# nola8.net
KiCad netlist of a schematic drawn in EAGLE
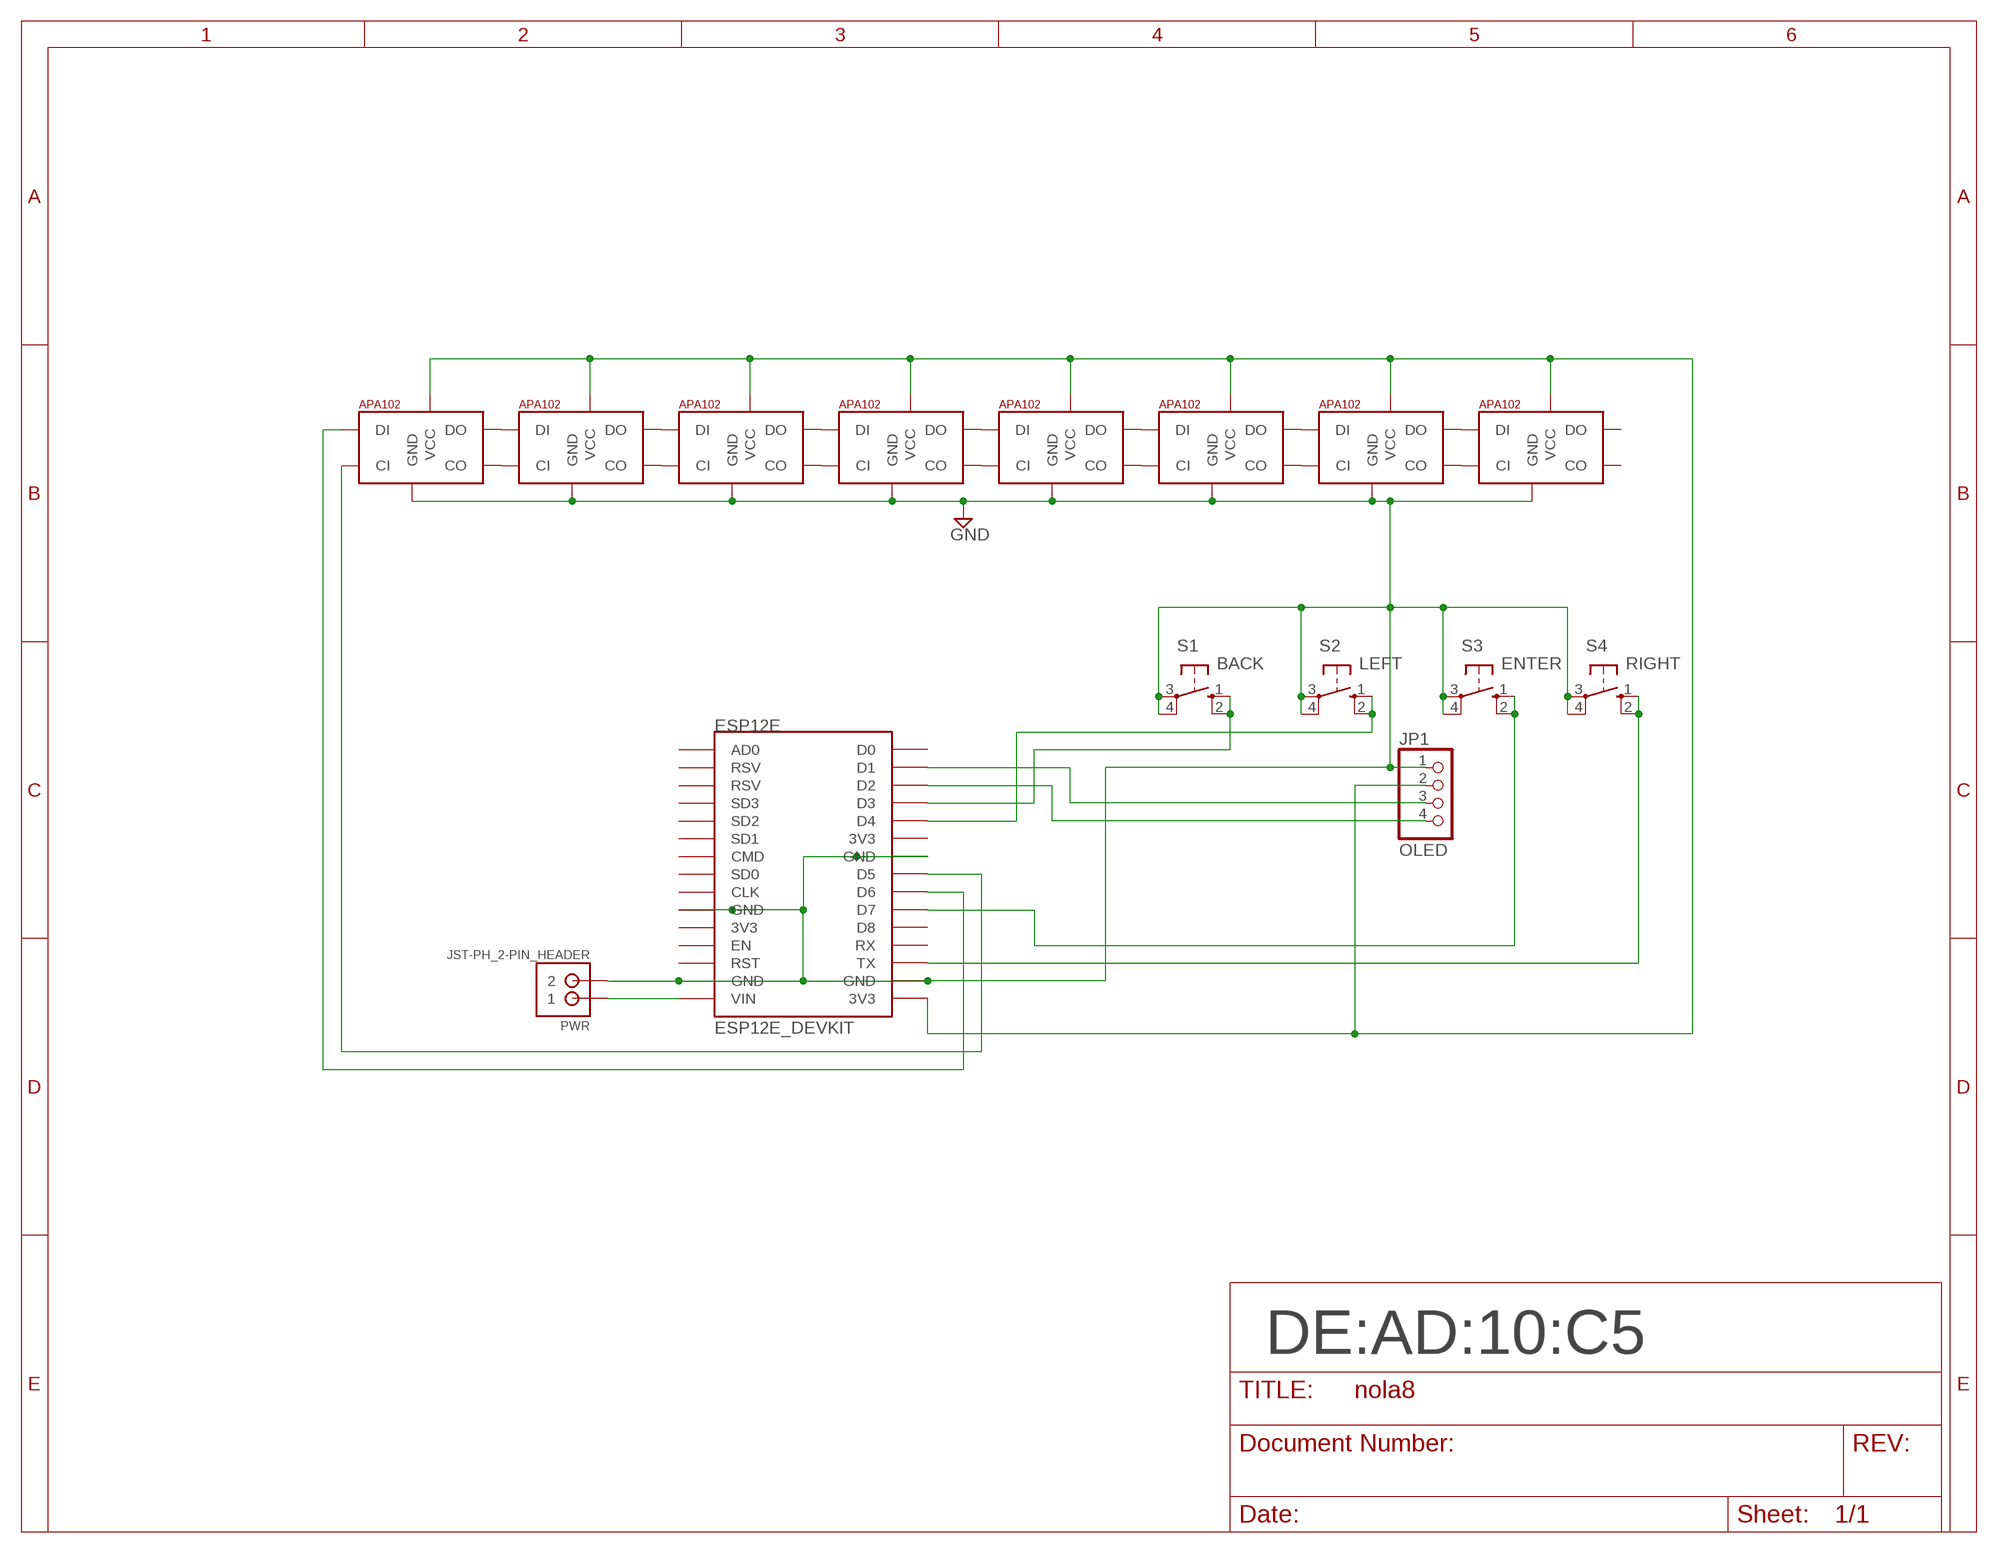
[diagram p0: schematic, sheet 1]

(export (version "E")
  (design (tool "Eeschema 10.0.6"))
  (components
    (comp (ref "ESP12E")
      (value "ESP12E_DEVKIT")
      (footprint "eagle-import:ESP12E_DEVKIT")
      (libsource (lib "eagle-import") (part "ESP12E_DEVKIT"))
    )
    (comp (ref "JP1")
      (value "OLED")
      (footprint "eagle-import:1X04")
      (libsource (lib "eagle-import") (part "PINHD-1X4"))
    )
    (comp (ref "LED1")
      (value "APA1025050")
      (footprint "eagle-import:APA102_5050")
      (libsource (lib "eagle-import") (part "APA1025050"))
    )
    (comp (ref "LED2")
      (value "APA1025050")
      (footprint "eagle-import:APA102_5050")
      (libsource (lib "eagle-import") (part "APA1025050"))
    )
    (comp (ref "LED3")
      (value "APA1025050")
      (footprint "eagle-import:APA102_5050")
      (libsource (lib "eagle-import") (part "APA1025050"))
    )
    (comp (ref "LED4")
      (value "APA1025050")
      (footprint "eagle-import:APA102_5050")
      (libsource (lib "eagle-import") (part "APA1025050"))
    )
    (comp (ref "LED5")
      (value "APA1025050")
      (footprint "eagle-import:APA102_5050")
      (libsource (lib "eagle-import") (part "APA1025050"))
    )
    (comp (ref "LED6")
      (value "APA1025050")
      (footprint "eagle-import:APA102_5050")
      (libsource (lib "eagle-import") (part "APA1025050"))
    )
    (comp (ref "LED7")
      (value "APA1025050")
      (footprint "eagle-import:APA102_5050")
      (libsource (lib "eagle-import") (part "APA1025050"))
    )
    (comp (ref "LED8")
      (value "APA1025050")
      (footprint "eagle-import:APA102_5050")
      (libsource (lib "eagle-import") (part "APA1025050"))
    )
    (comp (ref "PWR")
      (value "JST-PH_2-PIN_HEADER")
      (footprint "eagle-import:JST_B2B-PH_HEADER")
      (libsource (lib "eagle-import") (part "JST-PH_2-PIN_HEADER"))
    )
    (comp (ref "S1")
      (value "BACK")
      (footprint "eagle-import:B3F-10XX")
      (fields (field (name "MPN") "B3F-1000"))
      (libsource (lib "eagle-import") (part "10-XX"))
    )
    (comp (ref "S2")
      (value "LEFT")
      (footprint "eagle-import:B3F-10XX")
      (fields (field (name "MPN") "B3F-1000"))
      (libsource (lib "eagle-import") (part "10-XX"))
    )
    (comp (ref "S3")
      (value "ENTER")
      (footprint "eagle-import:B3F-10XX")
      (fields (field (name "MPN") "B3F-1000"))
      (libsource (lib "eagle-import") (part "10-XX"))
    )
    (comp (ref "S4")
      (value "RIGHT")
      (footprint "eagle-import:B3F-10XX")
      (fields (field (name "MPN") "B3F-1000"))
      (libsource (lib "eagle-import") (part "10-XX"))
    )
  )
  (nets
    (net (code "1") (name "GND") (class "Default")
      (node (ref "ESP12E") (pin "GND@0") (pinfunction "GND_GND@0") (pintype "bidirectional"))
      (node (ref "ESP12E") (pin "GND@1") (pinfunction "GND_GND@1") (pintype "bidirectional"))
      (node (ref "ESP12E") (pin "GND@2") (pinfunction "GND_GND@2") (pintype "bidirectional"))
      (node (ref "ESP12E") (pin "GND@3") (pinfunction "GND_GND@3") (pintype "bidirectional"))
      (node (ref "JP1") (pin "1") (pinfunction "1_1") (pintype "passive"))
      (node (ref "LED1") (pin "6") (pinfunction "GND_6") (pintype "bidirectional"))
      (node (ref "LED2") (pin "6") (pinfunction "GND_6") (pintype "bidirectional"))
      (node (ref "LED3") (pin "6") (pinfunction "GND_6") (pintype "bidirectional"))
      (node (ref "LED4") (pin "6") (pinfunction "GND_6") (pintype "bidirectional"))
      (node (ref "LED5") (pin "6") (pinfunction "GND_6") (pintype "bidirectional"))
      (node (ref "LED6") (pin "6") (pinfunction "GND_6") (pintype "bidirectional"))
      (node (ref "LED7") (pin "6") (pinfunction "GND_6") (pintype "bidirectional"))
      (node (ref "LED8") (pin "6") (pinfunction "GND_6") (pintype "bidirectional"))
      (node (ref "PWR") (pin "P2") (pinfunction "2_P2") (pintype "bidirectional"))
      (node (ref "S1") (pin "3") (pinfunction "P_3") (pintype "passive"))
      (node (ref "S1") (pin "4") (pinfunction "P1_4") (pintype "passive"))
      (node (ref "S2") (pin "3") (pinfunction "P_3") (pintype "passive"))
      (node (ref "S2") (pin "4") (pinfunction "P1_4") (pintype "passive"))
      (node (ref "S3") (pin "3") (pinfunction "P_3") (pintype "passive"))
      (node (ref "S3") (pin "4") (pinfunction "P1_4") (pintype "passive"))
      (node (ref "S4") (pin "3") (pinfunction "P_3") (pintype "passive"))
      (node (ref "S4") (pin "4") (pinfunction "P1_4") (pintype "passive"))
    )
    (net (code "2") (name "Net-(ESP12E-PadD1)") (class "Default")
      (node (ref "ESP12E") (pin "D1") (pinfunction "D1_D1") (pintype "bidirectional"))
      (node (ref "JP1") (pin "3") (pinfunction "3_3") (pintype "passive"))
    )
    (net (code "3") (name "Net-(ESP12E-PadD2)") (class "Default")
      (node (ref "ESP12E") (pin "D2") (pinfunction "D2_D2") (pintype "bidirectional"))
      (node (ref "JP1") (pin "4") (pinfunction "4_4") (pintype "passive"))
    )
    (net (code "4") (name "Net-(LED1-CI)") (class "Default")
      (node (ref "ESP12E") (pin "D5") (pinfunction "D5_D5") (pintype "bidirectional"))
      (node (ref "LED1") (pin "5") (pinfunction "CI_5") (pintype "bidirectional"))
    )
    (net (code "5") (name "Net-(LED1-CO)") (class "Default")
      (node (ref "LED1") (pin "2") (pinfunction "CO_2") (pintype "bidirectional"))
      (node (ref "LED2") (pin "5") (pinfunction "CI_5") (pintype "bidirectional"))
    )
    (net (code "6") (name "Net-(LED1-DI)") (class "Default")
      (node (ref "ESP12E") (pin "D6") (pinfunction "D6_D6") (pintype "bidirectional"))
      (node (ref "LED1") (pin "4") (pinfunction "DI_4") (pintype "bidirectional"))
    )
    (net (code "7") (name "Net-(LED1-DO)") (class "Default")
      (node (ref "LED1") (pin "3") (pinfunction "DO_3") (pintype "bidirectional"))
      (node (ref "LED2") (pin "4") (pinfunction "DI_4") (pintype "bidirectional"))
    )
    (net (code "8") (name "Net-(LED1-VCC)") (class "Default")
      (node (ref "ESP12E") (pin "3V3@2") (pinfunction "3V3_3V3@2") (pintype "bidirectional"))
      (node (ref "JP1") (pin "2") (pinfunction "2_2") (pintype "passive"))
      (node (ref "LED1") (pin "1") (pinfunction "VCC_1") (pintype "bidirectional"))
      (node (ref "LED2") (pin "1") (pinfunction "VCC_1") (pintype "bidirectional"))
      (node (ref "LED3") (pin "1") (pinfunction "VCC_1") (pintype "bidirectional"))
      (node (ref "LED4") (pin "1") (pinfunction "VCC_1") (pintype "bidirectional"))
      (node (ref "LED5") (pin "1") (pinfunction "VCC_1") (pintype "bidirectional"))
      (node (ref "LED6") (pin "1") (pinfunction "VCC_1") (pintype "bidirectional"))
      (node (ref "LED7") (pin "1") (pinfunction "VCC_1") (pintype "bidirectional"))
      (node (ref "LED8") (pin "1") (pinfunction "VCC_1") (pintype "bidirectional"))
    )
    (net (code "9") (name "Net-(LED2-CO)") (class "Default")
      (node (ref "LED2") (pin "2") (pinfunction "CO_2") (pintype "bidirectional"))
      (node (ref "LED3") (pin "5") (pinfunction "CI_5") (pintype "bidirectional"))
    )
    (net (code "10") (name "Net-(LED2-DO)") (class "Default")
      (node (ref "LED2") (pin "3") (pinfunction "DO_3") (pintype "bidirectional"))
      (node (ref "LED3") (pin "4") (pinfunction "DI_4") (pintype "bidirectional"))
    )
    (net (code "11") (name "Net-(LED3-CO)") (class "Default")
      (node (ref "LED3") (pin "2") (pinfunction "CO_2") (pintype "bidirectional"))
      (node (ref "LED4") (pin "5") (pinfunction "CI_5") (pintype "bidirectional"))
    )
    (net (code "12") (name "Net-(LED3-DO)") (class "Default")
      (node (ref "LED3") (pin "3") (pinfunction "DO_3") (pintype "bidirectional"))
      (node (ref "LED4") (pin "4") (pinfunction "DI_4") (pintype "bidirectional"))
    )
    (net (code "13") (name "Net-(LED4-CO)") (class "Default")
      (node (ref "LED4") (pin "2") (pinfunction "CO_2") (pintype "bidirectional"))
      (node (ref "LED5") (pin "5") (pinfunction "CI_5") (pintype "bidirectional"))
    )
    (net (code "14") (name "Net-(LED4-DO)") (class "Default")
      (node (ref "LED4") (pin "3") (pinfunction "DO_3") (pintype "bidirectional"))
      (node (ref "LED5") (pin "4") (pinfunction "DI_4") (pintype "bidirectional"))
    )
    (net (code "15") (name "Net-(LED5-CO)") (class "Default")
      (node (ref "LED5") (pin "2") (pinfunction "CO_2") (pintype "bidirectional"))
      (node (ref "LED6") (pin "5") (pinfunction "CI_5") (pintype "bidirectional"))
    )
    (net (code "16") (name "Net-(LED5-DO)") (class "Default")
      (node (ref "LED5") (pin "3") (pinfunction "DO_3") (pintype "bidirectional"))
      (node (ref "LED6") (pin "4") (pinfunction "DI_4") (pintype "bidirectional"))
    )
    (net (code "17") (name "Net-(LED6-CO)") (class "Default")
      (node (ref "LED6") (pin "2") (pinfunction "CO_2") (pintype "bidirectional"))
      (node (ref "LED7") (pin "5") (pinfunction "CI_5") (pintype "bidirectional"))
    )
    (net (code "18") (name "Net-(LED6-DO)") (class "Default")
      (node (ref "LED6") (pin "3") (pinfunction "DO_3") (pintype "bidirectional"))
      (node (ref "LED7") (pin "4") (pinfunction "DI_4") (pintype "bidirectional"))
    )
    (net (code "19") (name "Net-(LED7-CO)") (class "Default")
      (node (ref "LED7") (pin "2") (pinfunction "CO_2") (pintype "bidirectional"))
      (node (ref "LED8") (pin "5") (pinfunction "CI_5") (pintype "bidirectional"))
    )
    (net (code "20") (name "Net-(LED7-DO)") (class "Default")
      (node (ref "LED7") (pin "3") (pinfunction "DO_3") (pintype "bidirectional"))
      (node (ref "LED8") (pin "4") (pinfunction "DI_4") (pintype "bidirectional"))
    )
    (net (code "21") (name "Net-(PWR-1)") (class "Default")
      (node (ref "ESP12E") (pin "VIN") (pinfunction "VIN_VIN") (pintype "bidirectional"))
      (node (ref "PWR") (pin "P1") (pinfunction "1_P1") (pintype "bidirectional"))
    )
    (net (code "22") (name "Net-(S1-S)") (class "Default")
      (node (ref "ESP12E") (pin "D3") (pinfunction "D3_D3") (pintype "bidirectional"))
      (node (ref "S1") (pin "1") (pinfunction "S_1") (pintype "passive"))
      (node (ref "S1") (pin "2") (pinfunction "S1_2") (pintype "passive"))
    )
    (net (code "23") (name "Net-(S2-S)") (class "Default")
      (node (ref "ESP12E") (pin "D4") (pinfunction "D4_D4") (pintype "bidirectional"))
      (node (ref "S2") (pin "1") (pinfunction "S_1") (pintype "passive"))
      (node (ref "S2") (pin "2") (pinfunction "S1_2") (pintype "passive"))
    )
    (net (code "24") (name "Net-(S3-S)") (class "Default")
      (node (ref "ESP12E") (pin "D7") (pinfunction "D7_D7") (pintype "bidirectional"))
      (node (ref "S3") (pin "1") (pinfunction "S_1") (pintype "passive"))
      (node (ref "S3") (pin "2") (pinfunction "S1_2") (pintype "passive"))
    )
    (net (code "25") (name "Net-(S4-S)") (class "Default")
      (node (ref "ESP12E") (pin "TX") (pinfunction "TX_TX") (pintype "bidirectional"))
      (node (ref "S4") (pin "1") (pinfunction "S_1") (pintype "passive"))
      (node (ref "S4") (pin "2") (pinfunction "S1_2") (pintype "passive"))
    )
    (net (code "26") (name "unconnected-(ESP12E-3V3-Pad3V3@0)") (class "Default")
      (node (ref "ESP12E") (pin "3V3@0") (pinfunction "3V3_3V3@0") (pintype "bidirectional"))
    )
    (net (code "27") (name "unconnected-(ESP12E-3V3-Pad3V3@1)") (class "Default")
      (node (ref "ESP12E") (pin "3V3@1") (pinfunction "3V3_3V3@1") (pintype "bidirectional"))
    )
    (net (code "28") (name "unconnected-(ESP12E-PadAD0)") (class "Default")
      (node (ref "ESP12E") (pin "AD0") (pinfunction "AD0_AD0") (pintype "bidirectional"))
    )
    (net (code "29") (name "unconnected-(ESP12E-PadCLK)") (class "Default")
      (node (ref "ESP12E") (pin "CLK") (pinfunction "CLK_CLK") (pintype "bidirectional"))
    )
    (net (code "30") (name "unconnected-(ESP12E-PadCMD)") (class "Default")
      (node (ref "ESP12E") (pin "CMD") (pinfunction "CMD_CMD") (pintype "bidirectional"))
    )
    (net (code "31") (name "unconnected-(ESP12E-PadD0)") (class "Default")
      (node (ref "ESP12E") (pin "D0") (pinfunction "D0_D0") (pintype "bidirectional"))
    )
    (net (code "32") (name "unconnected-(ESP12E-PadD8)") (class "Default")
      (node (ref "ESP12E") (pin "D8") (pinfunction "D8_D8") (pintype "bidirectional"))
    )
    (net (code "33") (name "unconnected-(ESP12E-PadEN)") (class "Default")
      (node (ref "ESP12E") (pin "EN") (pinfunction "EN_EN") (pintype "bidirectional"))
    )
    (net (code "34") (name "unconnected-(ESP12E-PadRST)") (class "Default")
      (node (ref "ESP12E") (pin "RST") (pinfunction "RST_RST") (pintype "bidirectional"))
    )
    (net (code "35") (name "unconnected-(ESP12E-PadRX)") (class "Default")
      (node (ref "ESP12E") (pin "RX") (pinfunction "RX_RX") (pintype "bidirectional"))
    )
    (net (code "36") (name "unconnected-(ESP12E-PadSD0)") (class "Default")
      (node (ref "ESP12E") (pin "SD0") (pinfunction "SD0_SD0") (pintype "bidirectional"))
    )
    (net (code "37") (name "unconnected-(ESP12E-PadSD1)") (class "Default")
      (node (ref "ESP12E") (pin "SD1") (pinfunction "SD1_SD1") (pintype "bidirectional"))
    )
    (net (code "38") (name "unconnected-(ESP12E-PadSD2)") (class "Default")
      (node (ref "ESP12E") (pin "SD2") (pinfunction "SD2_SD2") (pintype "bidirectional"))
    )
    (net (code "39") (name "unconnected-(ESP12E-PadSD3)") (class "Default")
      (node (ref "ESP12E") (pin "SD3") (pinfunction "SD3_SD3") (pintype "bidirectional"))
    )
    (net (code "40") (name "unconnected-(ESP12E-RSV-PadRSV@0)") (class "Default")
      (node (ref "ESP12E") (pin "RSV@0") (pinfunction "RSV_RSV@0") (pintype "bidirectional"))
    )
    (net (code "41") (name "unconnected-(ESP12E-RSV-PadRSV@1)") (class "Default")
      (node (ref "ESP12E") (pin "RSV@1") (pinfunction "RSV_RSV@1") (pintype "bidirectional"))
    )
    (net (code "42") (name "unconnected-(LED8-CO-Pad2)") (class "Default")
      (node (ref "LED8") (pin "2") (pinfunction "CO_2") (pintype "bidirectional"))
    )
    (net (code "43") (name "unconnected-(LED8-DO-Pad3)") (class "Default")
      (node (ref "LED8") (pin "3") (pinfunction "DO_3") (pintype "bidirectional"))
    )
  )
)
